# SD.net
KiCad netlist of a schematic drawn in Altium Designer
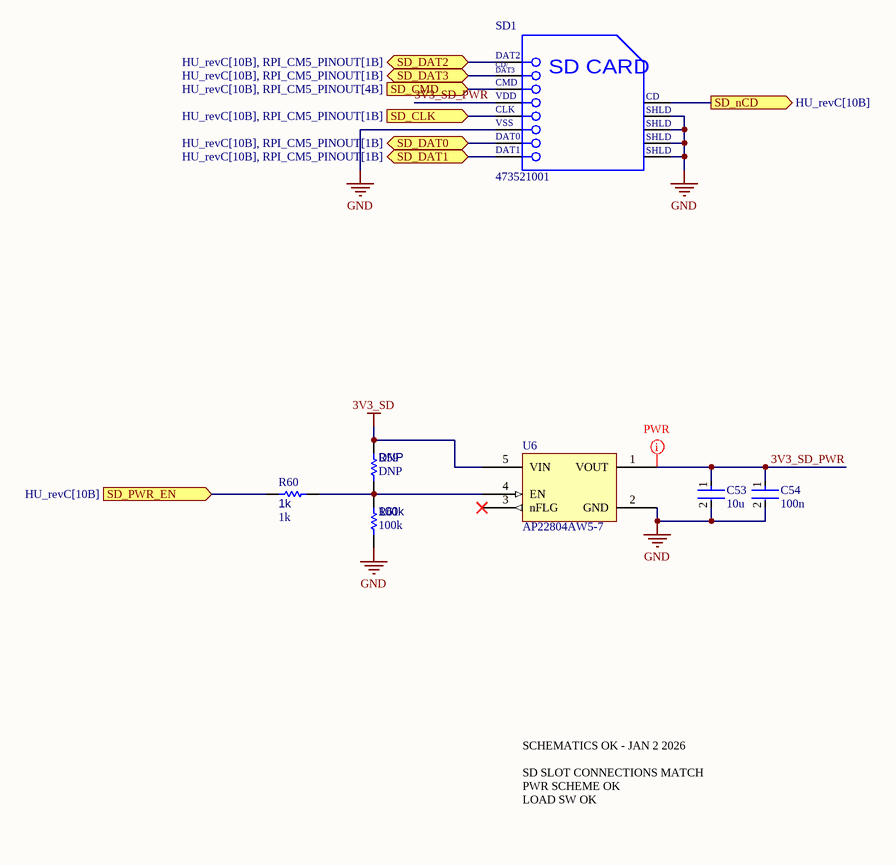
[diagram p0: SD.SchDoc]

(export (version "E")
  (design (tool "Eeschema 10.0.6"))
  (components
    (comp (ref "C53")
      (value "10u")
      (footprint "FP-0402-L_1_0_0_05-W_0_5-IPC_A")
      (description "LARGE PADS, 0402 CAP, CHANGE COMMENT TO MATCH REAL P/N")
      (libsource (lib "Space Concordia") (part "b4654b650e69147ec39a6b967a45e02"))
    )
    (comp (ref "C54")
      (value "100n")
      (footprint "FP-0402-L_1_0_0_05-W_0_5-IPC_A")
      (description "LARGE PADS, 0402 CAP, CHANGE COMMENT TO MATCH REAL P/N")
      (libsource (lib "Space Concordia") (part "b4654b650e69147ec39a6b967a45e02"))
    )
    (comp (ref "R59")
      (value "DNP")
      (footprint "R0603B")
      (description "Resistor")
      (fields (field (name "ALTIUM_VALUE") "DNP"))
      (libsource (lib "Space Concordia") (part "Resistor"))
    )
    (comp (ref "R60")
      (value "1k")
      (footprint "R0603B")
      (description "Resistor")
      (fields (field (name "ALTIUM_VALUE") "1k"))
      (libsource (lib "Space Concordia") (part "Resistor"))
    )
    (comp (ref "R61")
      (value "100k")
      (footprint "R0603B")
      (description "Resistor")
      (fields (field (name "ALTIUM_VALUE") "100k"))
      (libsource (lib "Space Concordia") (part "Resistor"))
    )
    (comp (ref "SD1")
      (value "473521001")
      (footprint "MOLX-473521001_V")
      (description "MicroSD(TM), Pitch 1.1 mm, 8 Position, Height 1.88 mm, -20 to 85 degC, RoHS, Tape and Reel")
      (fields (field (name "MANUFACTURER") "Molex"))
      (libsource (lib "Altium Content Vault") (part "CN-SD-8-1SW-4S"))
    )
    (comp (ref "U6")
      (value "AP22804AW5-7")
      (footprint "SOT95P285X140-5N")
      (description "SINGLE CHANNEL POWER DISTRIBUTION LOAD SWITCH, -40 to 85°C pF, RoHS")
      (libsource (lib "Space Concordia") (part "AP22804AW5-7"))
    )
  )
  (nets
    (net (code "1") (name "/3V3_SD_PWR") (class "Default")
      (node (ref "C53") (pin "1") (pinfunction "1_1") (pintype "passive"))
      (node (ref "C54") (pin "1") (pinfunction "1_1") (pintype "passive"))
      (node (ref "SD1") (pin "4") (pinfunction "VDD_4") (pintype "passive"))
      (node (ref "U6") (pin "1") (pinfunction "VOUT_1") (pintype "power_in"))
    )
    (net (code "2") (name "/SD_CLK") (class "Default")
      (node (ref "SD1") (pin "5") (pinfunction "CLK_5") (pintype "passive"))
    )
    (net (code "3") (name "/SD_CMD") (class "Default")
      (node (ref "SD1") (pin "3") (pinfunction "CMD_3") (pintype "passive"))
    )
    (net (code "4") (name "/SD_DAT0") (class "Default")
      (node (ref "SD1") (pin "7") (pinfunction "DAT0_7") (pintype "passive"))
    )
    (net (code "5") (name "/SD_DAT1") (class "Default")
      (node (ref "SD1") (pin "8") (pinfunction "DAT1_8") (pintype "passive"))
    )
    (net (code "6") (name "/SD_DAT2") (class "Default")
      (node (ref "SD1") (pin "1") (pinfunction "DAT2_1") (pintype "passive"))
    )
    (net (code "7") (name "/SD_DAT3") (class "Default")
      (node (ref "SD1") (pin "2") (pinfunction "CD/DAT3_2") (pintype "passive"))
    )
    (net (code "8") (name "/SD_PWR_EN") (class "Default")
      (node (ref "R60") (pin "2") (pinfunction "2_2") (pintype "passive"))
    )
    (net (code "9") (name "/SD_nCD") (class "Default")
      (node (ref "SD1") (pin "9") (pinfunction "CD_9") (pintype "passive"))
    )
    (net (code "10") (name "3V3_SD") (class "Default")
      (node (ref "R59") (pin "2") (pinfunction "2_2") (pintype "passive"))
      (node (ref "U6") (pin "5") (pinfunction "VIN_5") (pintype "power_in"))
    )
    (net (code "11") (name "GND") (class "Default")
      (node (ref "C53") (pin "2") (pinfunction "2_2") (pintype "passive"))
      (node (ref "C54") (pin "2") (pinfunction "2_2") (pintype "passive"))
      (node (ref "R61") (pin "1") (pinfunction "1_1") (pintype "passive"))
      (node (ref "SD1") (pin "10") (pinfunction "SHLD_10") (pintype "passive"))
      (node (ref "SD1") (pin "11") (pinfunction "SHLD_11") (pintype "passive"))
      (node (ref "SD1") (pin "12") (pinfunction "SHLD_12") (pintype "passive"))
      (node (ref "SD1") (pin "13") (pinfunction "SHLD_13") (pintype "passive"))
      (node (ref "SD1") (pin "6") (pinfunction "VSS_6") (pintype "passive"))
      (node (ref "U6") (pin "2") (pinfunction "GND_2") (pintype "power_in"))
    )
    (net (code "12") (name "Net-(U6-EN)") (class "Default")
      (node (ref "R59") (pin "1") (pinfunction "1_1") (pintype "passive"))
      (node (ref "R60") (pin "1") (pinfunction "1_1") (pintype "passive"))
      (node (ref "R61") (pin "2") (pinfunction "2_2") (pintype "passive"))
      (node (ref "U6") (pin "4") (pinfunction "EN_4") (pintype "input"))
    )
    (net (code "13") (name "unconnected-(U6-nFLG-Pad3)") (class "Default")
      (node (ref "U6") (pin "3") (pinfunction "nFLG_3") (pintype "output+no_connect"))
    )
  )
)
